# Thermocouple_to_Digital_Converter.net
KiCad netlist of a schematic drawn in Altium Designer
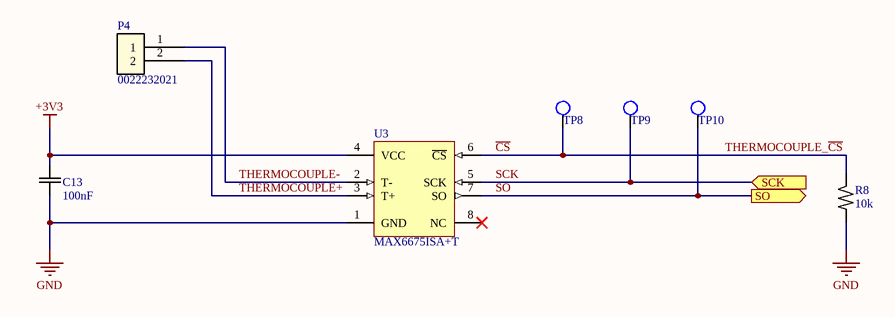
[diagram p0: Thermocouple to Digital Converter.SchDoc]

(export (version "E")
  (design (tool "Eeschema 10.0.6"))
  (components
    (comp (ref "C13")
      (value "100nF")
      (footprint "C0603")
      (description "CAP CER 100nF 50V X7R 0603")
      (fields (field (name "MF") "HRE") (field (name "MP") "CGA0603X7R104K500JT"))
      (libsource (lib "Components") (part "Cap_cer"))
    )
    (comp (ref "P4")
      (value "0022232021")
      (footprint "Signal2")
      (description "SignalConnector, 2 leads")
      (fields (field (name "MF") "Molex"))
      (libsource (lib "Connectors") (part "Signal2"))
    )
    (comp (ref "R8")
      (value "10k")
      (footprint "R0603")
      (description "RES 10kΩ ±1% 100mW 0603")
      (fields (field (name "MF") "FOJAN") (field (name "MP") "FRC0603F1002TS"))
      (libsource (lib "Components") (part "Res"))
    )
    (comp (ref "TP8")
      (value "TestPoint")
      (footprint "TESTPOINT_SMD_1.27MM")
      (libsource (lib "Components") (part "TestPoint"))
    )
    (comp (ref "TP9")
      (value "TestPoint")
      (footprint "TESTPOINT_SMD_1.27MM")
      (libsource (lib "Components") (part "TestPoint"))
    )
    (comp (ref "TP10")
      (value "TestPoint")
      (footprint "TESTPOINT_SMD_1.27MM")
      (libsource (lib "Components") (part "TestPoint"))
    )
    (comp (ref "U3")
      (value "MAX6675ISA+T")
      (footprint "SOIC-8")
      (description "Cold-Junction-Compensated K-Thermocouple-to-Digital Converter")
      (fields (field (name "MF") "MAXIM"))
      (libsource (lib "Components") (part "MAX6675ISA+T"))
    )
  )
  (nets
    (net (code "1") (name "+3V3") (class "Default")
      (node (ref "C13") (pin "2") (pinfunction "2_2") (pintype "passive"))
      (node (ref "U3") (pin "4") (pinfunction "VCC_4") (pintype "power_in"))
    )
    (net (code "2") (name "/SCK") (class "Default")
      (node (ref "TP9") (pin "1") (pinfunction "1_1") (pintype "passive"))
      (node (ref "U3") (pin "5") (pinfunction "SCK_5") (pintype "input"))
    )
    (net (code "3") (name "/SO") (class "Default")
      (node (ref "TP10") (pin "1") (pinfunction "1_1") (pintype "passive"))
      (node (ref "U3") (pin "7") (pinfunction "SO_7") (pintype "output"))
    )
    (net (code "4") (name "/THERMOCOUPLE+") (class "Default")
      (node (ref "P4") (pin "2") (pinfunction "2_2") (pintype "passive"))
      (node (ref "U3") (pin "3") (pinfunction "T+_3") (pintype "input"))
    )
    (net (code "5") (name "/THERMOCOUPLE-") (class "Default")
      (node (ref "P4") (pin "1") (pinfunction "1_1") (pintype "passive"))
      (node (ref "U3") (pin "2") (pinfunction "T-_2") (pintype "input"))
    )
    (net (code "6") (name "/THERMOCOUPLE_~{CS}") (class "Default")
      (node (ref "R8") (pin "2") (pinfunction "2_2") (pintype "passive"))
      (node (ref "TP8") (pin "1") (pinfunction "1_1") (pintype "passive"))
      (node (ref "U3") (pin "6") (pinfunction "~{CS}_6") (pintype "input"))
    )
    (net (code "7") (name "GND") (class "Default")
      (node (ref "C13") (pin "1") (pinfunction "1_1") (pintype "passive"))
      (node (ref "R8") (pin "1") (pinfunction "1_1") (pintype "passive"))
      (node (ref "U3") (pin "1") (pinfunction "GND_1") (pintype "power_in"))
    )
    (net (code "8") (name "unconnected-(U3-NC-Pad8)") (class "Default")
      (node (ref "U3") (pin "8") (pinfunction "NC_8") (pintype "passive+no_connect"))
    )
  )
)
